# Colpitt_s_Oscillator.net
KiCad netlist of a schematic drawn in EasyEDA
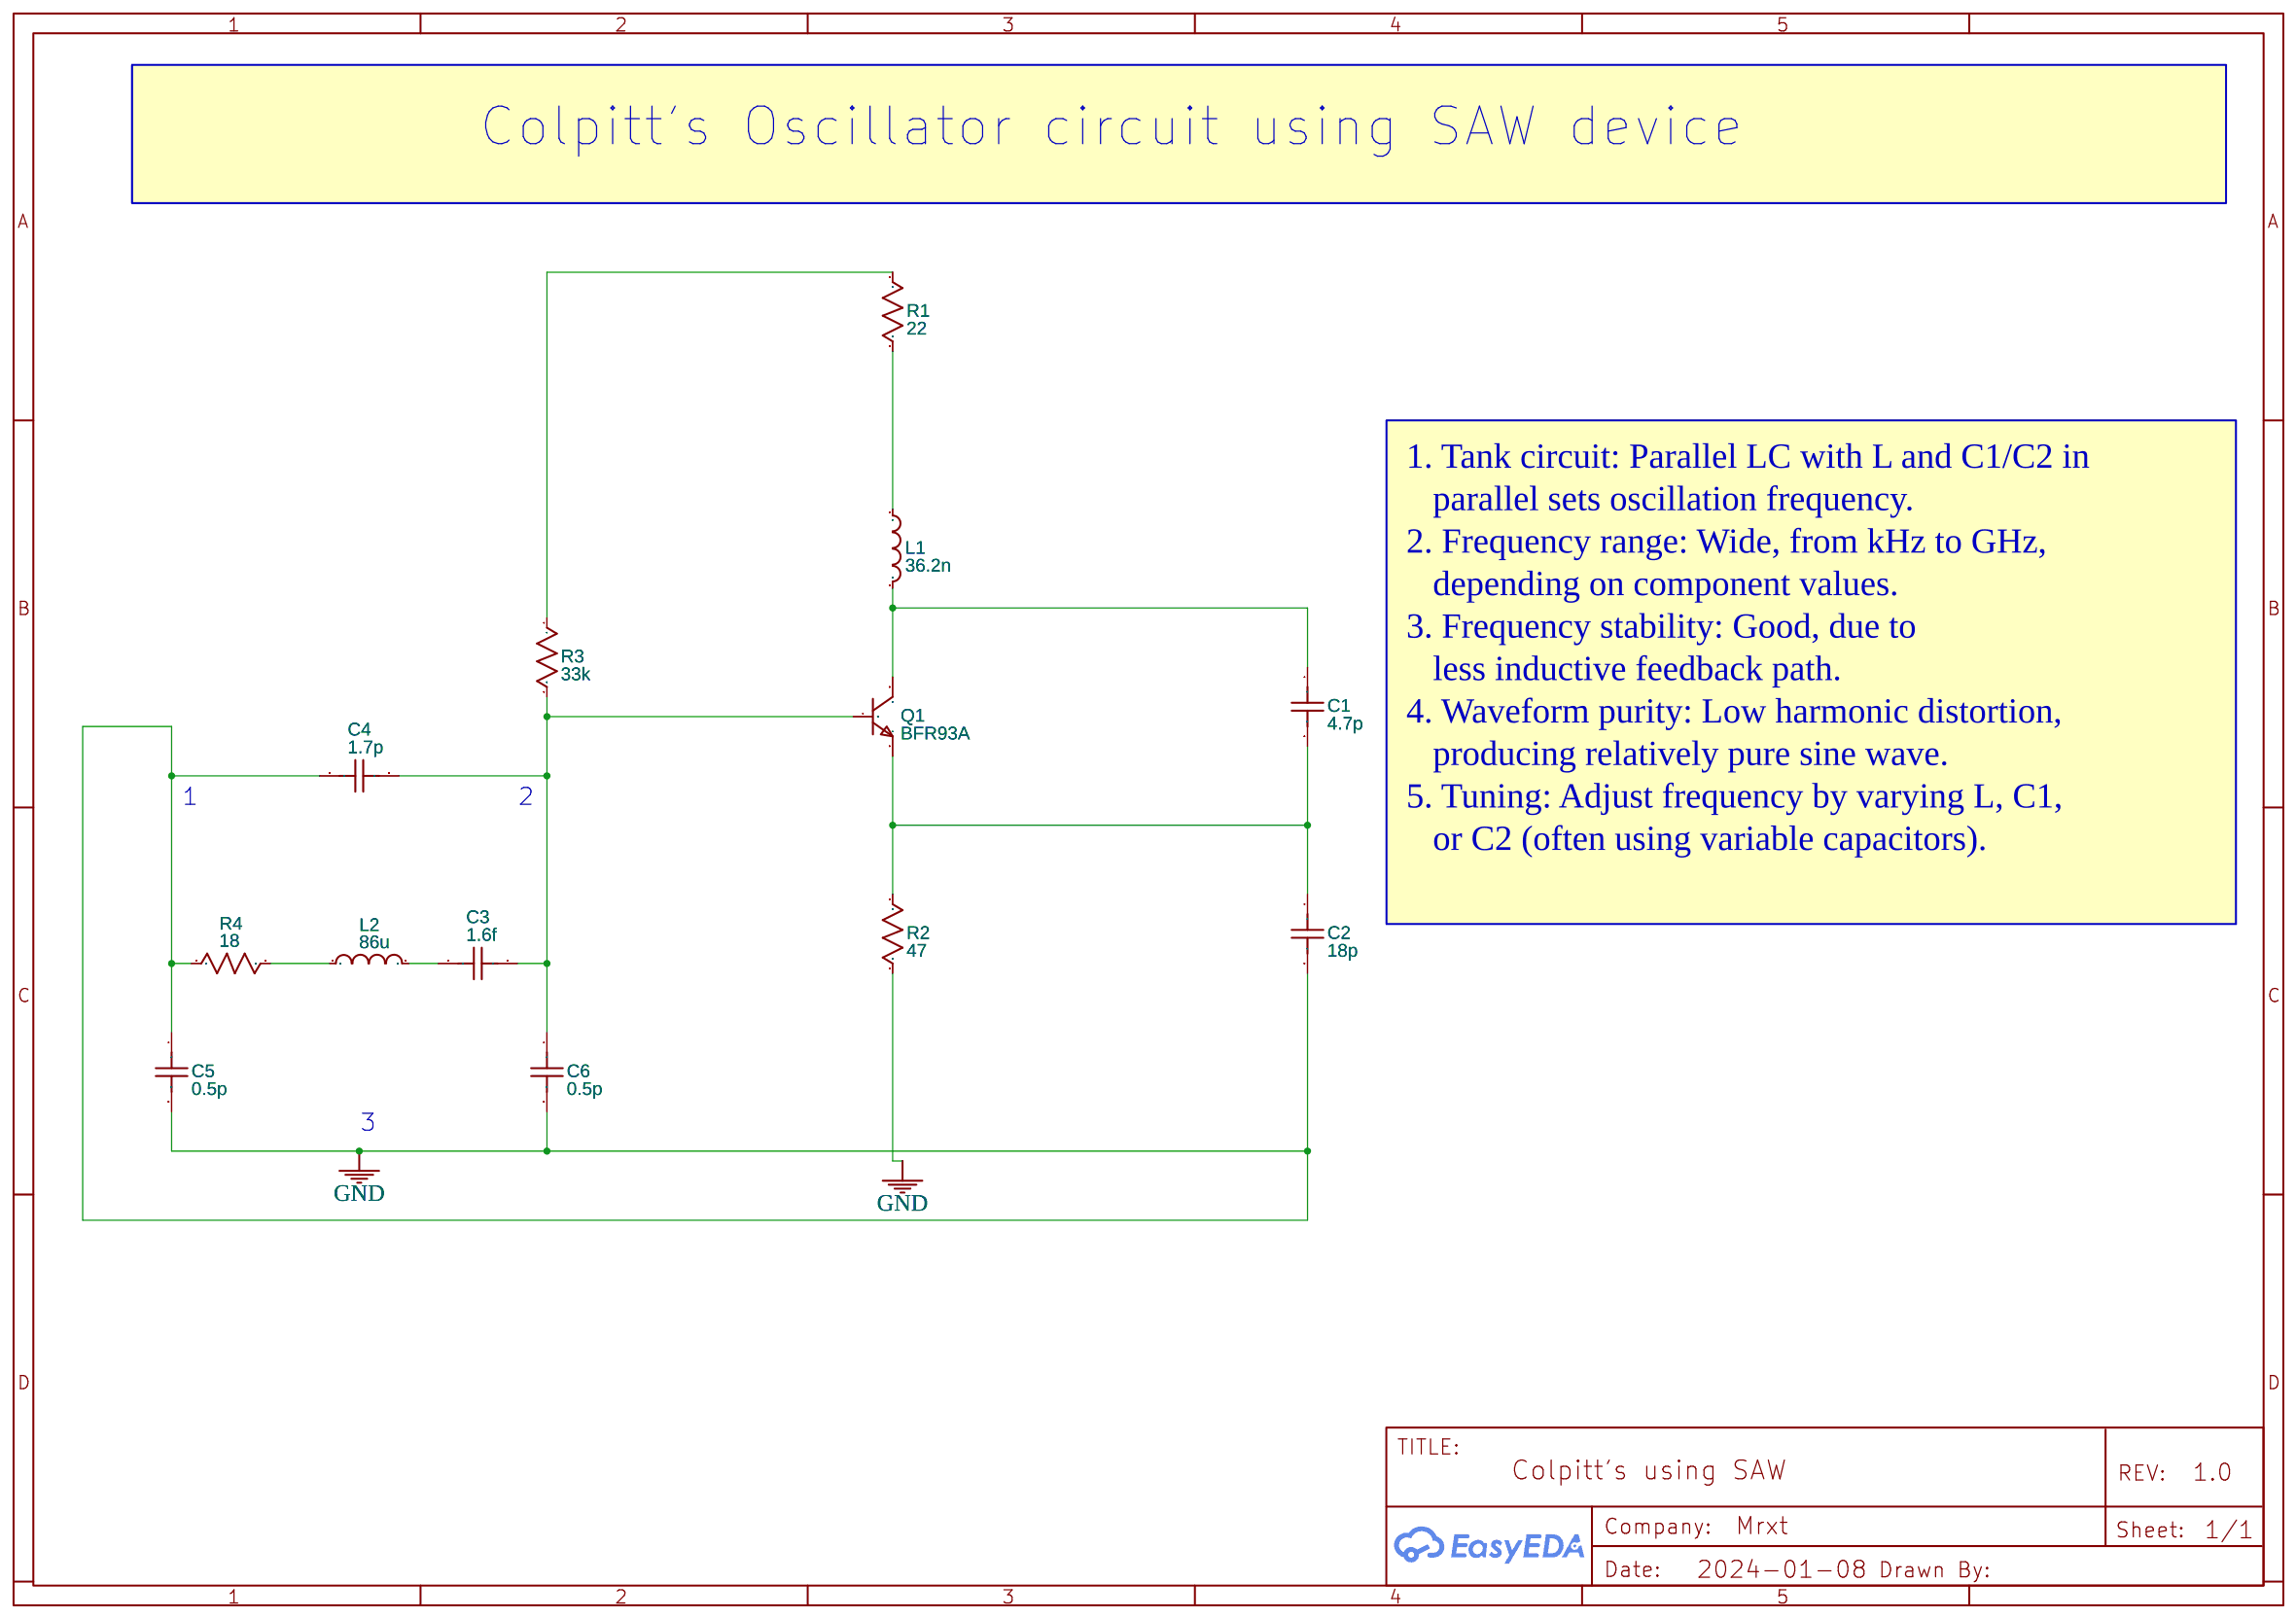
[diagram p0: schematic sheet]

(export (version "E")
  (design (tool "Eeschema 10.0.6"))
  (components
    (comp (ref "C1") (value "4.7p") (libsource (lib "") (part "C_0402_US_1")))
    (comp (ref "C2") (value "18p") (libsource (lib "") (part "C_0402_US_1")))
    (comp (ref "C3") (value "1.6f") (libsource (lib "") (part "C_0402_US")))
    (comp (ref "C4") (value "1.7p") (libsource (lib "") (part "C_0402_US")))
    (comp (ref "C5") (value "0.5p") (libsource (lib "") (part "C_0402_US_1")))
    (comp (ref "C6") (value "0.5p") (libsource (lib "") (part "C_0402_US_1")))
    (comp (ref "L1") (value "36.2n") (libsource (lib "") (part "L0402_US")))
    (comp (ref "L2") (value "86u") (libsource (lib "") (part "L0402_US_1")))
    (comp (ref "Q1")
      (value "BFR93A")
      (fields (field (name "Manufacturer Part") "BFR93AWH6327") (field (name "Manufacturer") "Infineon(英飞凌)"))
      (libsource (lib "") (part "BFR93AWH6327XTSA1"))
    )
    (comp (ref "R1") (value "22") (libsource (lib "") (part "R_0402_US")))
    (comp (ref "R2") (value "47") (libsource (lib "") (part "R_0402_US")))
    (comp (ref "R3") (value "33k") (libsource (lib "") (part "R_0402_US")))
    (comp (ref "R4") (value "18") (libsource (lib "") (part "R_0402_US_1")))
  )
  (nets
    (net (code "1") (name "GND") (class "Default")
      (node (ref "C2") (pin "2") (pinfunction "2_2") (pintype "unspecified"))
      (node (ref "C4") (pin "1") (pinfunction "1_1") (pintype "unspecified"))
      (node (ref "C5") (pin "1") (pinfunction "1_1") (pintype "unspecified"))
      (node (ref "C5") (pin "2") (pinfunction "2_2") (pintype "unspecified"))
      (node (ref "C6") (pin "2") (pinfunction "2_2") (pintype "unspecified"))
      (node (ref "R2") (pin "2") (pinfunction "2_2") (pintype "unspecified"))
      (node (ref "R4") (pin "1") (pinfunction "1_1") (pintype "unspecified"))
    )
    (net (code "2") (name "Net-(C3-Pad1)") (class "Default")
      (node (ref "C3") (pin "1") (pinfunction "1_1") (pintype "unspecified"))
      (node (ref "L2") (pin "2") (pinfunction "2_2") (pintype "unspecified"))
    )
    (net (code "3") (name "Net-(L1-Pad1)") (class "Default")
      (node (ref "L1") (pin "1") (pinfunction "1_1") (pintype "unspecified"))
      (node (ref "R1") (pin "2") (pinfunction "2_2") (pintype "unspecified"))
    )
    (net (code "4") (name "Net-(L2-Pad1)") (class "Default")
      (node (ref "L2") (pin "1") (pinfunction "1_1") (pintype "unspecified"))
      (node (ref "R4") (pin "2") (pinfunction "2_2") (pintype "unspecified"))
    )
    (net (code "5") (name "Net-(Q1-B)") (class "Default")
      (node (ref "C3") (pin "2") (pinfunction "2_2") (pintype "unspecified"))
      (node (ref "C4") (pin "2") (pinfunction "2_2") (pintype "unspecified"))
      (node (ref "C6") (pin "1") (pinfunction "1_1") (pintype "unspecified"))
      (node (ref "Q1") (pin "1") (pinfunction "B_1") (pintype "unspecified"))
      (node (ref "R3") (pin "2") (pinfunction "2_2") (pintype "unspecified"))
    )
    (net (code "6") (name "Net-(Q1-C)") (class "Default")
      (node (ref "C1") (pin "1") (pinfunction "1_1") (pintype "unspecified"))
      (node (ref "L1") (pin "2") (pinfunction "2_2") (pintype "unspecified"))
      (node (ref "Q1") (pin "3") (pinfunction "C_3") (pintype "unspecified"))
    )
    (net (code "7") (name "Net-(Q1-E)") (class "Default")
      (node (ref "C1") (pin "2") (pinfunction "2_2") (pintype "unspecified"))
      (node (ref "C2") (pin "1") (pinfunction "1_1") (pintype "unspecified"))
      (node (ref "Q1") (pin "2") (pinfunction "E_2") (pintype "unspecified"))
      (node (ref "R2") (pin "1") (pinfunction "1_1") (pintype "unspecified"))
    )
    (net (code "8") (name "Net-(R1-Pad1)") (class "Default")
      (node (ref "R1") (pin "1") (pinfunction "1_1") (pintype "unspecified"))
      (node (ref "R3") (pin "1") (pinfunction "1_1") (pintype "unspecified"))
    )
  )
)
